# AUX_POWER_V2.net
KiCad netlist of a schematic drawn in Altium Designer
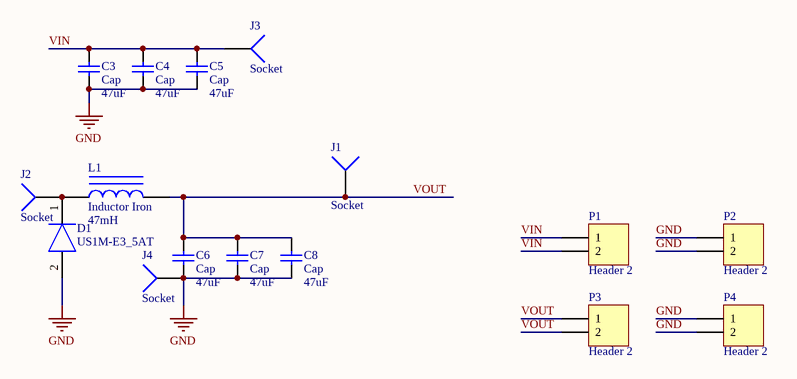
[diagram p0: AUX_POWER_V2.SchDoc]

(export (version "E")
  (design (tool "Eeschema 10.0.6"))
  (components
    (comp (ref "C3")
      (value "Cap")
      (footprint "C1210")
      (description "Capacitor")
      (fields (field (name "ALTIUM_VALUE") "47uF") (field (name "PUBLISHER") "Altium Limited"))
      (libsource (lib "Miscellaneous Devices") (part "Cap"))
    )
    (comp (ref "C4")
      (value "Cap")
      (footprint "C1210")
      (description "Capacitor")
      (fields (field (name "ALTIUM_VALUE") "47uF") (field (name "PUBLISHER") "Altium Limited"))
      (libsource (lib "Miscellaneous Devices") (part "Cap"))
    )
    (comp (ref "C5")
      (value "Cap")
      (footprint "C1210")
      (description "Capacitor")
      (fields (field (name "ALTIUM_VALUE") "47uF") (field (name "PUBLISHER") "Altium Limited"))
      (libsource (lib "Miscellaneous Devices") (part "Cap"))
    )
    (comp (ref "C6")
      (value "Cap")
      (footprint "C1210")
      (description "Capacitor")
      (fields (field (name "ALTIUM_VALUE") "47uF") (field (name "PUBLISHER") "Altium Limited"))
      (libsource (lib "Miscellaneous Devices") (part "Cap"))
    )
    (comp (ref "C7")
      (value "Cap")
      (footprint "C1210")
      (description "Capacitor")
      (fields (field (name "ALTIUM_VALUE") "47uF") (field (name "PUBLISHER") "Altium Limited"))
      (libsource (lib "Miscellaneous Devices") (part "Cap"))
    )
    (comp (ref "C8")
      (value "Cap")
      (footprint "C1210")
      (description "Capacitor")
      (fields (field (name "ALTIUM_VALUE") "47uF") (field (name "PUBLISHER") "Altium Limited"))
      (libsource (lib "Miscellaneous Devices") (part "Cap"))
    )
    (comp (ref "D1")
      (value "US1M-E3_5AT")
      (footprint "SamacSys:DIOM5127X229N")
      (description "Diode")
      (fields
        (field (name "MANUFACTURER_PART_NUMBER") "US1M-E3/5AT")
        (field (name "MOUSER PART NUMBER") "625-US1M-E3/5AT")
      )
      (libsource (lib "*") (part "US1M-E3_5AT"))
    )
    (comp (ref "J1")
      (value "Socket")
      (footprint "PIN1")
      (fields (field (name "PUBLISHER") "Altium Limited"))
      (libsource (lib "Miscellaneous Connectors") (part "Socket"))
    )
    (comp (ref "J2")
      (value "Socket")
      (footprint "PIN1")
      (fields (field (name "PUBLISHER") "Altium Limited"))
      (libsource (lib "Miscellaneous Connectors") (part "Socket"))
    )
    (comp (ref "J3")
      (value "Socket")
      (footprint "PIN1")
      (fields (field (name "PUBLISHER") "Altium Limited"))
      (libsource (lib "Miscellaneous Connectors") (part "Socket"))
    )
    (comp (ref "J4")
      (value "Socket")
      (footprint "PIN1")
      (fields (field (name "PUBLISHER") "Altium Limited"))
      (libsource (lib "Miscellaneous Connectors") (part "Socket"))
    )
    (comp (ref "L1")
      (value "Inductor Iron")
      (footprint "CDRH127")
      (description "Magnetic-Core Inductor")
      (fields (field (name "ALTIUM_VALUE") "47mH") (field (name "PUBLISHER") "Altium Limited"))
      (libsource (lib "Miscellaneous Devices") (part "Inductor Iron"))
    )
    (comp (ref "P1")
      (value "Header 2")
      (footprint "HDR1X2")
      (description "Header, 2-Pin")
      (fields (field (name "PUBLISHER") "Altium Limited"))
      (libsource (lib "Miscellaneous Connectors") (part "Header 2"))
    )
    (comp (ref "P2")
      (value "Header 2")
      (footprint "HDR1X2")
      (description "Header, 2-Pin")
      (fields (field (name "PUBLISHER") "Altium Limited"))
      (libsource (lib "Miscellaneous Connectors") (part "Header 2"))
    )
    (comp (ref "P3")
      (value "Header 2")
      (footprint "HDR1X2")
      (description "Header, 2-Pin")
      (fields (field (name "PUBLISHER") "Altium Limited"))
      (libsource (lib "Miscellaneous Connectors") (part "Header 2"))
    )
    (comp (ref "P4")
      (value "Header 2")
      (footprint "HDR1X2")
      (description "Header, 2-Pin")
      (fields (field (name "PUBLISHER") "Altium Limited"))
      (libsource (lib "Miscellaneous Connectors") (part "Header 2"))
    )
  )
  (nets
    (net (code "1") (name "/VIN") (class "Default")
      (node (ref "C3") (pin "2") (pinfunction "2_2") (pintype "passive"))
      (node (ref "C4") (pin "2") (pinfunction "2_2") (pintype "passive"))
      (node (ref "C5") (pin "2") (pinfunction "2_2") (pintype "passive"))
      (node (ref "J3") (pin "1") (pinfunction "1_1") (pintype "passive"))
      (node (ref "P1") (pin "1") (pinfunction "1_1") (pintype "passive"))
      (node (ref "P1") (pin "2") (pinfunction "2_2") (pintype "passive"))
    )
    (net (code "2") (name "/VOUT") (class "Default")
      (node (ref "C6") (pin "2") (pinfunction "2_2") (pintype "passive"))
      (node (ref "C7") (pin "2") (pinfunction "2_2") (pintype "passive"))
      (node (ref "C8") (pin "2") (pinfunction "2_2") (pintype "passive"))
      (node (ref "J1") (pin "1") (pinfunction "1_1") (pintype "passive"))
      (node (ref "L1") (pin "2") (pinfunction "2_2") (pintype "passive"))
      (node (ref "P3") (pin "1") (pinfunction "1_1") (pintype "passive"))
      (node (ref "P3") (pin "2") (pinfunction "2_2") (pintype "passive"))
    )
    (net (code "3") (name "GND") (class "Default")
      (node (ref "C3") (pin "1") (pinfunction "1_1") (pintype "passive"))
      (node (ref "C4") (pin "1") (pinfunction "1_1") (pintype "passive"))
      (node (ref "C5") (pin "1") (pinfunction "1_1") (pintype "passive"))
      (node (ref "C6") (pin "1") (pinfunction "1_1") (pintype "passive"))
      (node (ref "C7") (pin "1") (pinfunction "1_1") (pintype "passive"))
      (node (ref "C8") (pin "1") (pinfunction "1_1") (pintype "passive"))
      (node (ref "D1") (pin "2") (pinfunction "A_2") (pintype "passive"))
      (node (ref "J4") (pin "1") (pinfunction "1_1") (pintype "passive"))
      (node (ref "P2") (pin "1") (pinfunction "1_1") (pintype "passive"))
      (node (ref "P2") (pin "2") (pinfunction "2_2") (pintype "passive"))
      (node (ref "P4") (pin "1") (pinfunction "1_1") (pintype "passive"))
      (node (ref "P4") (pin "2") (pinfunction "2_2") (pintype "passive"))
    )
    (net (code "4") (name "Net-(D1-K)") (class "Default")
      (node (ref "D1") (pin "1") (pinfunction "K_1") (pintype "passive"))
      (node (ref "J2") (pin "1") (pinfunction "1_1") (pintype "passive"))
      (node (ref "L1") (pin "1") (pinfunction "1_1") (pintype "passive"))
    )
  )
)
